# LM2596.net
KiCad netlist of a schematic drawn in EAGLE
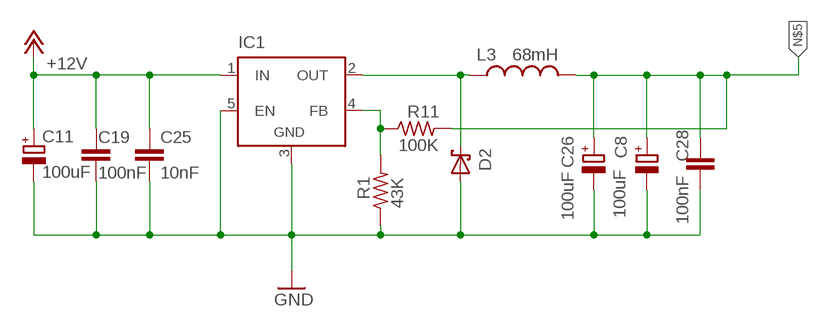
[diagram p0: schematic, sheet 1]

(export (version "E")
  (design (tool "Eeschema 10.0.6"))
  (components
    (comp (ref "C8")
      (value "100uF")
      (footprint "eagle-import:E2,5-7")
      (libsource (lib "eagle-import") (part "CPOL-EUE2.5-7"))
    )
    (comp (ref "C11")
      (value "100uF")
      (footprint "eagle-import:E2,5-7")
      (libsource (lib "eagle-import") (part "CPOL-EUE2.5-7"))
    )
    (comp (ref "C19")
      (value "100nF")
      (footprint "eagle-import:C050-024X044")
      (libsource (lib "eagle-import") (part "C-EU050-024X044"))
    )
    (comp (ref "C25")
      (value "10nF")
      (footprint "eagle-import:C050-024X044")
      (libsource (lib "eagle-import") (part "C-EU050-024X044"))
    )
    (comp (ref "C26")
      (value "100uF")
      (footprint "eagle-import:E2,5-7")
      (libsource (lib "eagle-import") (part "CPOL-EUE2.5-7"))
    )
    (comp (ref "C28")
      (value "100nF")
      (footprint "eagle-import:C050-024X044")
      (libsource (lib "eagle-import") (part "C-EU050-024X044"))
    )
    (comp (ref "D2")
      (value "SCHOTTKY-DIODEDO41")
      (footprint "eagle-import:DO41-10")
      (libsource (lib "eagle-import") (part "SCHOTTKY-DIODEDO41"))
    )
    (comp (ref "IC1")
      (value "LM2596TH")
      (footprint "eagle-import:TO220-52")
      (libsource (lib "eagle-import") (part "LM2596TH"))
    )
    (comp (ref "L3")
      (value "68mH")
      (footprint "eagle-import:0207_10")
      (libsource (lib "eagle-import") (part "L-US0207/10"))
    )
    (comp (ref "R1")
      (value "43K")
      (footprint "eagle-import:0204_7")
      (libsource (lib "eagle-import") (part "R-US_0204/7"))
    )
    (comp (ref "R11")
      (value "100K")
      (footprint "eagle-import:0204_7")
      (libsource (lib "eagle-import") (part "R-US_0204/7"))
    )
  )
  (nets
    (net (code "1") (name "+12V") (class "Default")
      (node (ref "C11") (pin "+") (pinfunction "+_+") (pintype "passive"))
      (node (ref "C19") (pin "1") (pinfunction "1_1") (pintype "passive"))
      (node (ref "C25") (pin "1") (pinfunction "1_1") (pintype "passive"))
      (node (ref "IC1") (pin "1") (pinfunction "IN_1") (pintype "input"))
    )
    (net (code "2") (name "GND") (class "Default")
      (node (ref "C11") (pin "-") (pinfunction "-_-") (pintype "passive"))
      (node (ref "C19") (pin "2") (pinfunction "2_2") (pintype "passive"))
      (node (ref "C25") (pin "2") (pinfunction "2_2") (pintype "passive"))
      (node (ref "C26") (pin "-") (pinfunction "-_-") (pintype "passive"))
      (node (ref "C28") (pin "2") (pinfunction "2_2") (pintype "passive"))
      (node (ref "C8") (pin "-") (pinfunction "-_-") (pintype "passive"))
      (node (ref "D2") (pin "A") (pinfunction "A_A") (pintype "passive"))
      (node (ref "IC1") (pin "3") (pinfunction "GND_3") (pintype "power_in"))
      (node (ref "IC1") (pin "5") (pinfunction "EN_5") (pintype "input"))
      (node (ref "R1") (pin "1") (pinfunction "1_1") (pintype "passive"))
    )
    (net (code "3") (name "N$5") (class "Default")
      (node (ref "C26") (pin "+") (pinfunction "+_+") (pintype "passive"))
      (node (ref "C28") (pin "1") (pinfunction "1_1") (pintype "passive"))
      (node (ref "C8") (pin "+") (pinfunction "+_+") (pintype "passive"))
      (node (ref "L3") (pin "2") (pinfunction "2_2") (pintype "passive"))
      (node (ref "R11") (pin "2") (pinfunction "2_2") (pintype "passive"))
    )
    (net (code "4") (name "Net-(IC1-FB)") (class "Default")
      (node (ref "IC1") (pin "4") (pinfunction "FB_4") (pintype "input"))
      (node (ref "R1") (pin "2") (pinfunction "2_2") (pintype "passive"))
      (node (ref "R11") (pin "1") (pinfunction "1_1") (pintype "passive"))
    )
    (net (code "5") (name "Net-(IC1-OUT)") (class "Default")
      (node (ref "D2") (pin "C") (pinfunction "C_C") (pintype "passive"))
      (node (ref "IC1") (pin "2") (pinfunction "OUT_2") (pintype "output"))
      (node (ref "L3") (pin "1") (pinfunction "1_1") (pintype "passive"))
    )
  )
)
